# BareBonesArduino.net
KiCad netlist of a schematic drawn in EAGLE
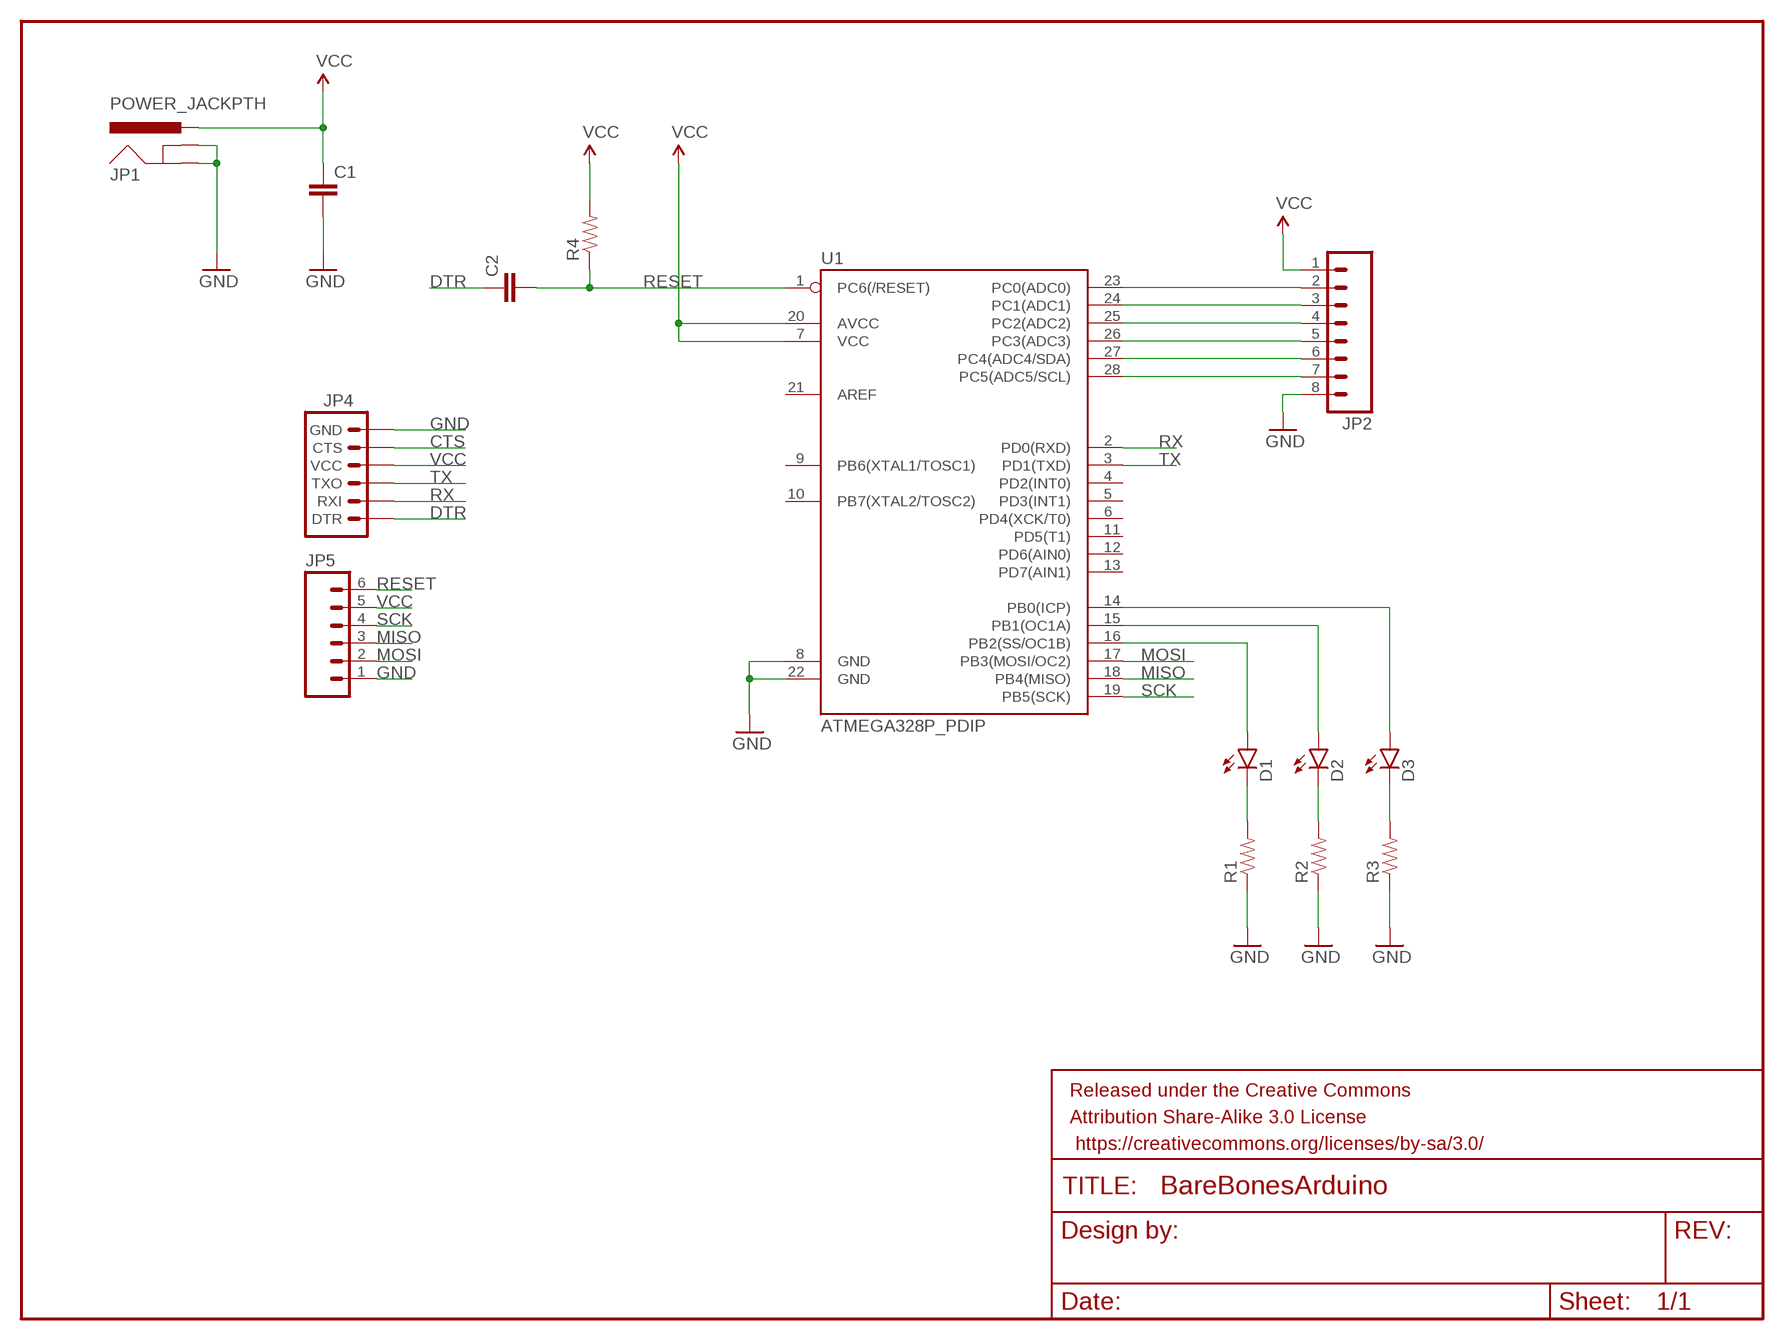
[diagram p0: schematic, sheet 1]

(export (version "E")
  (design (tool "Eeschema 10.0.6"))
  (components
    (comp (ref "C1")
      (value "CAPPTH")
      (footprint "eagle-import:CAP-PTH-SMALL")
      (libsource (lib "eagle-import") (part "CAPPTH"))
    )
    (comp (ref "C2")
      (value "CAPPTH")
      (footprint "eagle-import:CAP-PTH-SMALL")
      (libsource (lib "eagle-import") (part "CAPPTH"))
    )
    (comp (ref "D1")
      (value "LED5MM")
      (footprint "eagle-import:LED5MM")
      (libsource (lib "eagle-import") (part "LED5MM"))
    )
    (comp (ref "D2")
      (value "LED5MM")
      (footprint "eagle-import:LED5MM")
      (libsource (lib "eagle-import") (part "LED5MM"))
    )
    (comp (ref "D3")
      (value "LED5MM")
      (footprint "eagle-import:LED5MM")
      (libsource (lib "eagle-import") (part "LED5MM"))
    )
    (comp (ref "FRAME1")
      (value "FRAME-LETTER")
      (footprint "eagle-import:CREATIVE_COMMONS")
      (libsource (lib "eagle-import") (part "FRAME-LETTER"))
    )
    (comp (ref "JP1")
      (value "POWER_JACKPTH")
      (footprint "eagle-import:POWER_JACK_PTH")
      (libsource (lib "eagle-import") (part "POWER_JACKPTH"))
    )
    (comp (ref "JP2")
      (value "M08")
      (footprint "eagle-import:1X08_ROUND")
      (libsource (lib "eagle-import") (part "M08"))
    )
    (comp (ref "JP4")
      (value "ARDUINO_SERIAL_PROGRAMPTH")
      (footprint "eagle-import:1X06")
      (libsource (lib "eagle-import") (part "ARDUINO_SERIAL_PROGRAMPTH"))
    )
    (comp (ref "JP5")
      (value "M06SILK_FEMALE_PTH")
      (footprint "eagle-import:1X06")
      (libsource (lib "eagle-import") (part "M06SILK_FEMALE_PTH"))
    )
    (comp (ref "R1")
      (value "RESISTORPTH-1/4W")
      (footprint "eagle-import:AXIAL-0.4")
      (libsource (lib "eagle-import") (part "RESISTORPTH-1/4W"))
    )
    (comp (ref "R2")
      (value "RESISTORPTH-1/4W")
      (footprint "eagle-import:AXIAL-0.4")
      (libsource (lib "eagle-import") (part "RESISTORPTH-1/4W"))
    )
    (comp (ref "R3")
      (value "RESISTORPTH-1/4W")
      (footprint "eagle-import:AXIAL-0.4")
      (libsource (lib "eagle-import") (part "RESISTORPTH-1/4W"))
    )
    (comp (ref "R4")
      (value "RESISTORPTH-1/4W")
      (footprint "eagle-import:AXIAL-0.4")
      (libsource (lib "eagle-import") (part "RESISTORPTH-1/4W"))
    )
    (comp (ref "U1")
      (value "ATMEGA328P_PDIP")
      (footprint "eagle-import:DIL28-3")
      (libsource (lib "eagle-import") (part "ATMEGA328P_PDIP"))
    )
  )
  (nets
    (net (code "1") (name "/CTS") (class "Default")
      (node (ref "JP4") (pin "5") (pinfunction "CTS_5") (pintype "passive"))
    )
    (net (code "2") (name "/DTR") (class "Default")
      (node (ref "C2") (pin "1") (pinfunction "1_1") (pintype "passive"))
      (node (ref "JP4") (pin "1") (pinfunction "DTR_1") (pintype "passive"))
    )
    (net (code "3") (name "/MISO") (class "Default")
      (node (ref "JP5") (pin "3") (pinfunction "3_3") (pintype "passive"))
      (node (ref "U1") (pin "18") (pinfunction "PB4(MISO)_18") (pintype "bidirectional"))
    )
    (net (code "4") (name "/MOSI") (class "Default")
      (node (ref "JP5") (pin "2") (pinfunction "2_2") (pintype "passive"))
      (node (ref "U1") (pin "17") (pinfunction "PB3(MOSI/OC2)_17") (pintype "bidirectional"))
    )
    (net (code "5") (name "/RESET") (class "Default")
      (node (ref "C2") (pin "2") (pinfunction "2_2") (pintype "passive"))
      (node (ref "JP5") (pin "6") (pinfunction "6_6") (pintype "passive"))
      (node (ref "R4") (pin "P$1") (pinfunction "1_P$1") (pintype "passive"))
      (node (ref "U1") (pin "1") (pinfunction "PC6(/RESET)_1") (pintype "bidirectional"))
    )
    (net (code "6") (name "/RX") (class "Default")
      (node (ref "JP4") (pin "2") (pinfunction "RXI_2") (pintype "passive"))
      (node (ref "U1") (pin "2") (pinfunction "PD0(RXD)_2") (pintype "bidirectional"))
    )
    (net (code "7") (name "/SCK") (class "Default")
      (node (ref "JP5") (pin "4") (pinfunction "4_4") (pintype "passive"))
      (node (ref "U1") (pin "19") (pinfunction "PB5(SCK)_19") (pintype "bidirectional"))
    )
    (net (code "8") (name "/TX") (class "Default")
      (node (ref "JP4") (pin "3") (pinfunction "TXO_3") (pintype "passive"))
      (node (ref "U1") (pin "3") (pinfunction "PD1(TXD)_3") (pintype "bidirectional"))
    )
    (net (code "9") (name "GND") (class "Default")
      (node (ref "C1") (pin "2") (pinfunction "2_2") (pintype "passive"))
      (node (ref "JP1") (pin "GND") (pinfunction "GND_GND") (pintype "bidirectional"))
      (node (ref "JP1") (pin "GNDBREAK") (pinfunction "GNDBREAK_GNDBREAK") (pintype "bidirectional"))
      (node (ref "JP2") (pin "8") (pinfunction "8_8") (pintype "passive"))
      (node (ref "JP4") (pin "6") (pinfunction "GND_6") (pintype "passive"))
      (node (ref "JP5") (pin "1") (pinfunction "1_1") (pintype "passive"))
      (node (ref "R1") (pin "P$1") (pinfunction "1_P$1") (pintype "passive"))
      (node (ref "R2") (pin "P$1") (pinfunction "1_P$1") (pintype "passive"))
      (node (ref "R3") (pin "P$1") (pinfunction "1_P$1") (pintype "passive"))
      (node (ref "U1") (pin "22") (pinfunction "GND_22") (pintype "bidirectional"))
      (node (ref "U1") (pin "8") (pinfunction "GND_8") (pintype "bidirectional"))
    )
    (net (code "10") (name "Net-(D1-C)") (class "Default")
      (node (ref "D1") (pin "K") (pinfunction "C_K") (pintype "passive"))
      (node (ref "R1") (pin "P$2") (pinfunction "2_P$2") (pintype "passive"))
    )
    (net (code "11") (name "Net-(D2-C)") (class "Default")
      (node (ref "D2") (pin "K") (pinfunction "C_K") (pintype "passive"))
      (node (ref "R2") (pin "P$2") (pinfunction "2_P$2") (pintype "passive"))
    )
    (net (code "12") (name "Net-(D3-C)") (class "Default")
      (node (ref "D3") (pin "K") (pinfunction "C_K") (pintype "passive"))
      (node (ref "R3") (pin "P$2") (pinfunction "2_P$2") (pintype "passive"))
    )
    (net (code "13") (name "Net-(U1-PB0(ICP))") (class "Default")
      (node (ref "D3") (pin "A") (pinfunction "A_A") (pintype "passive"))
      (node (ref "U1") (pin "14") (pinfunction "PB0(ICP)_14") (pintype "bidirectional"))
    )
    (net (code "14") (name "Net-(U1-PB1(OC1A))") (class "Default")
      (node (ref "D2") (pin "A") (pinfunction "A_A") (pintype "passive"))
      (node (ref "U1") (pin "15") (pinfunction "PB1(OC1A)_15") (pintype "bidirectional"))
    )
    (net (code "15") (name "Net-(U1-PB2(SS{slash}OC1B))") (class "Default")
      (node (ref "D1") (pin "A") (pinfunction "A_A") (pintype "passive"))
      (node (ref "U1") (pin "16") (pinfunction "PB2(SS/OC1B)_16") (pintype "bidirectional"))
    )
    (net (code "16") (name "Net-(U1-PC0(ADC0))") (class "Default")
      (node (ref "JP2") (pin "2") (pinfunction "2_2") (pintype "passive"))
      (node (ref "U1") (pin "23") (pinfunction "PC0(ADC0)_23") (pintype "bidirectional"))
    )
    (net (code "17") (name "Net-(U1-PC1(ADC1))") (class "Default")
      (node (ref "JP2") (pin "3") (pinfunction "3_3") (pintype "passive"))
      (node (ref "U1") (pin "24") (pinfunction "PC1(ADC1)_24") (pintype "bidirectional"))
    )
    (net (code "18") (name "Net-(U1-PC2(ADC2))") (class "Default")
      (node (ref "JP2") (pin "4") (pinfunction "4_4") (pintype "passive"))
      (node (ref "U1") (pin "25") (pinfunction "PC2(ADC2)_25") (pintype "bidirectional"))
    )
    (net (code "19") (name "Net-(U1-PC3(ADC3))") (class "Default")
      (node (ref "JP2") (pin "5") (pinfunction "5_5") (pintype "passive"))
      (node (ref "U1") (pin "26") (pinfunction "PC3(ADC3)_26") (pintype "bidirectional"))
    )
    (net (code "20") (name "Net-(U1-PC4(ADC4{slash}SDA))") (class "Default")
      (node (ref "JP2") (pin "6") (pinfunction "6_6") (pintype "passive"))
      (node (ref "U1") (pin "27") (pinfunction "PC4(ADC4/SDA)_27") (pintype "bidirectional"))
    )
    (net (code "21") (name "Net-(U1-PC5(ADC5{slash}SCL))") (class "Default")
      (node (ref "JP2") (pin "7") (pinfunction "7_7") (pintype "passive"))
      (node (ref "U1") (pin "28") (pinfunction "PC5(ADC5/SCL)_28") (pintype "bidirectional"))
    )
    (net (code "22") (name "VCC") (class "Default")
      (node (ref "C1") (pin "1") (pinfunction "1_1") (pintype "passive"))
      (node (ref "JP1") (pin "PWR") (pinfunction "PWR_PWR") (pintype "bidirectional"))
      (node (ref "JP2") (pin "1") (pinfunction "1_1") (pintype "passive"))
      (node (ref "JP4") (pin "4") (pinfunction "VCC_4") (pintype "passive"))
      (node (ref "JP5") (pin "5") (pinfunction "5_5") (pintype "passive"))
      (node (ref "R4") (pin "P$2") (pinfunction "2_P$2") (pintype "passive"))
      (node (ref "U1") (pin "20") (pinfunction "AVCC_20") (pintype "bidirectional"))
      (node (ref "U1") (pin "7") (pinfunction "VCC_7") (pintype "bidirectional"))
    )
    (net (code "23") (name "unconnected-(U1-AREF-Pad21)") (class "Default")
      (node (ref "U1") (pin "21") (pinfunction "AREF_21") (pintype "bidirectional"))
    )
    (net (code "24") (name "unconnected-(U1-PB6(XTAL1{slash}TOSC1)-Pad9)") (class "Default")
      (node (ref "U1") (pin "9") (pinfunction "PB6(XTAL1/TOSC1)_9") (pintype "bidirectional"))
    )
    (net (code "25") (name "unconnected-(U1-PB7(XTAL2{slash}TOSC2)-Pad10)") (class "Default")
      (node (ref "U1") (pin "10") (pinfunction "PB7(XTAL2/TOSC2)_10") (pintype "bidirectional"))
    )
    (net (code "26") (name "unconnected-(U1-PD2(INT0)-Pad4)") (class "Default")
      (node (ref "U1") (pin "4") (pinfunction "PD2(INT0)_4") (pintype "bidirectional"))
    )
    (net (code "27") (name "unconnected-(U1-PD3(INT1)-Pad5)") (class "Default")
      (node (ref "U1") (pin "5") (pinfunction "PD3(INT1)_5") (pintype "bidirectional"))
    )
    (net (code "28") (name "unconnected-(U1-PD4(XCK{slash}T0)-Pad6)") (class "Default")
      (node (ref "U1") (pin "6") (pinfunction "PD4(XCK/T0)_6") (pintype "bidirectional"))
    )
    (net (code "29") (name "unconnected-(U1-PD5(T1)-Pad11)") (class "Default")
      (node (ref "U1") (pin "11") (pinfunction "PD5(T1)_11") (pintype "bidirectional"))
    )
    (net (code "30") (name "unconnected-(U1-PD6(AIN0)-Pad12)") (class "Default")
      (node (ref "U1") (pin "12") (pinfunction "PD6(AIN0)_12") (pintype "bidirectional"))
    )
    (net (code "31") (name "unconnected-(U1-PD7(AIN1)-Pad13)") (class "Default")
      (node (ref "U1") (pin "13") (pinfunction "PD7(AIN1)_13") (pintype "bidirectional"))
    )
  )
)
